# 101_Power.net
KiCad netlist of a schematic drawn in Altium Designer
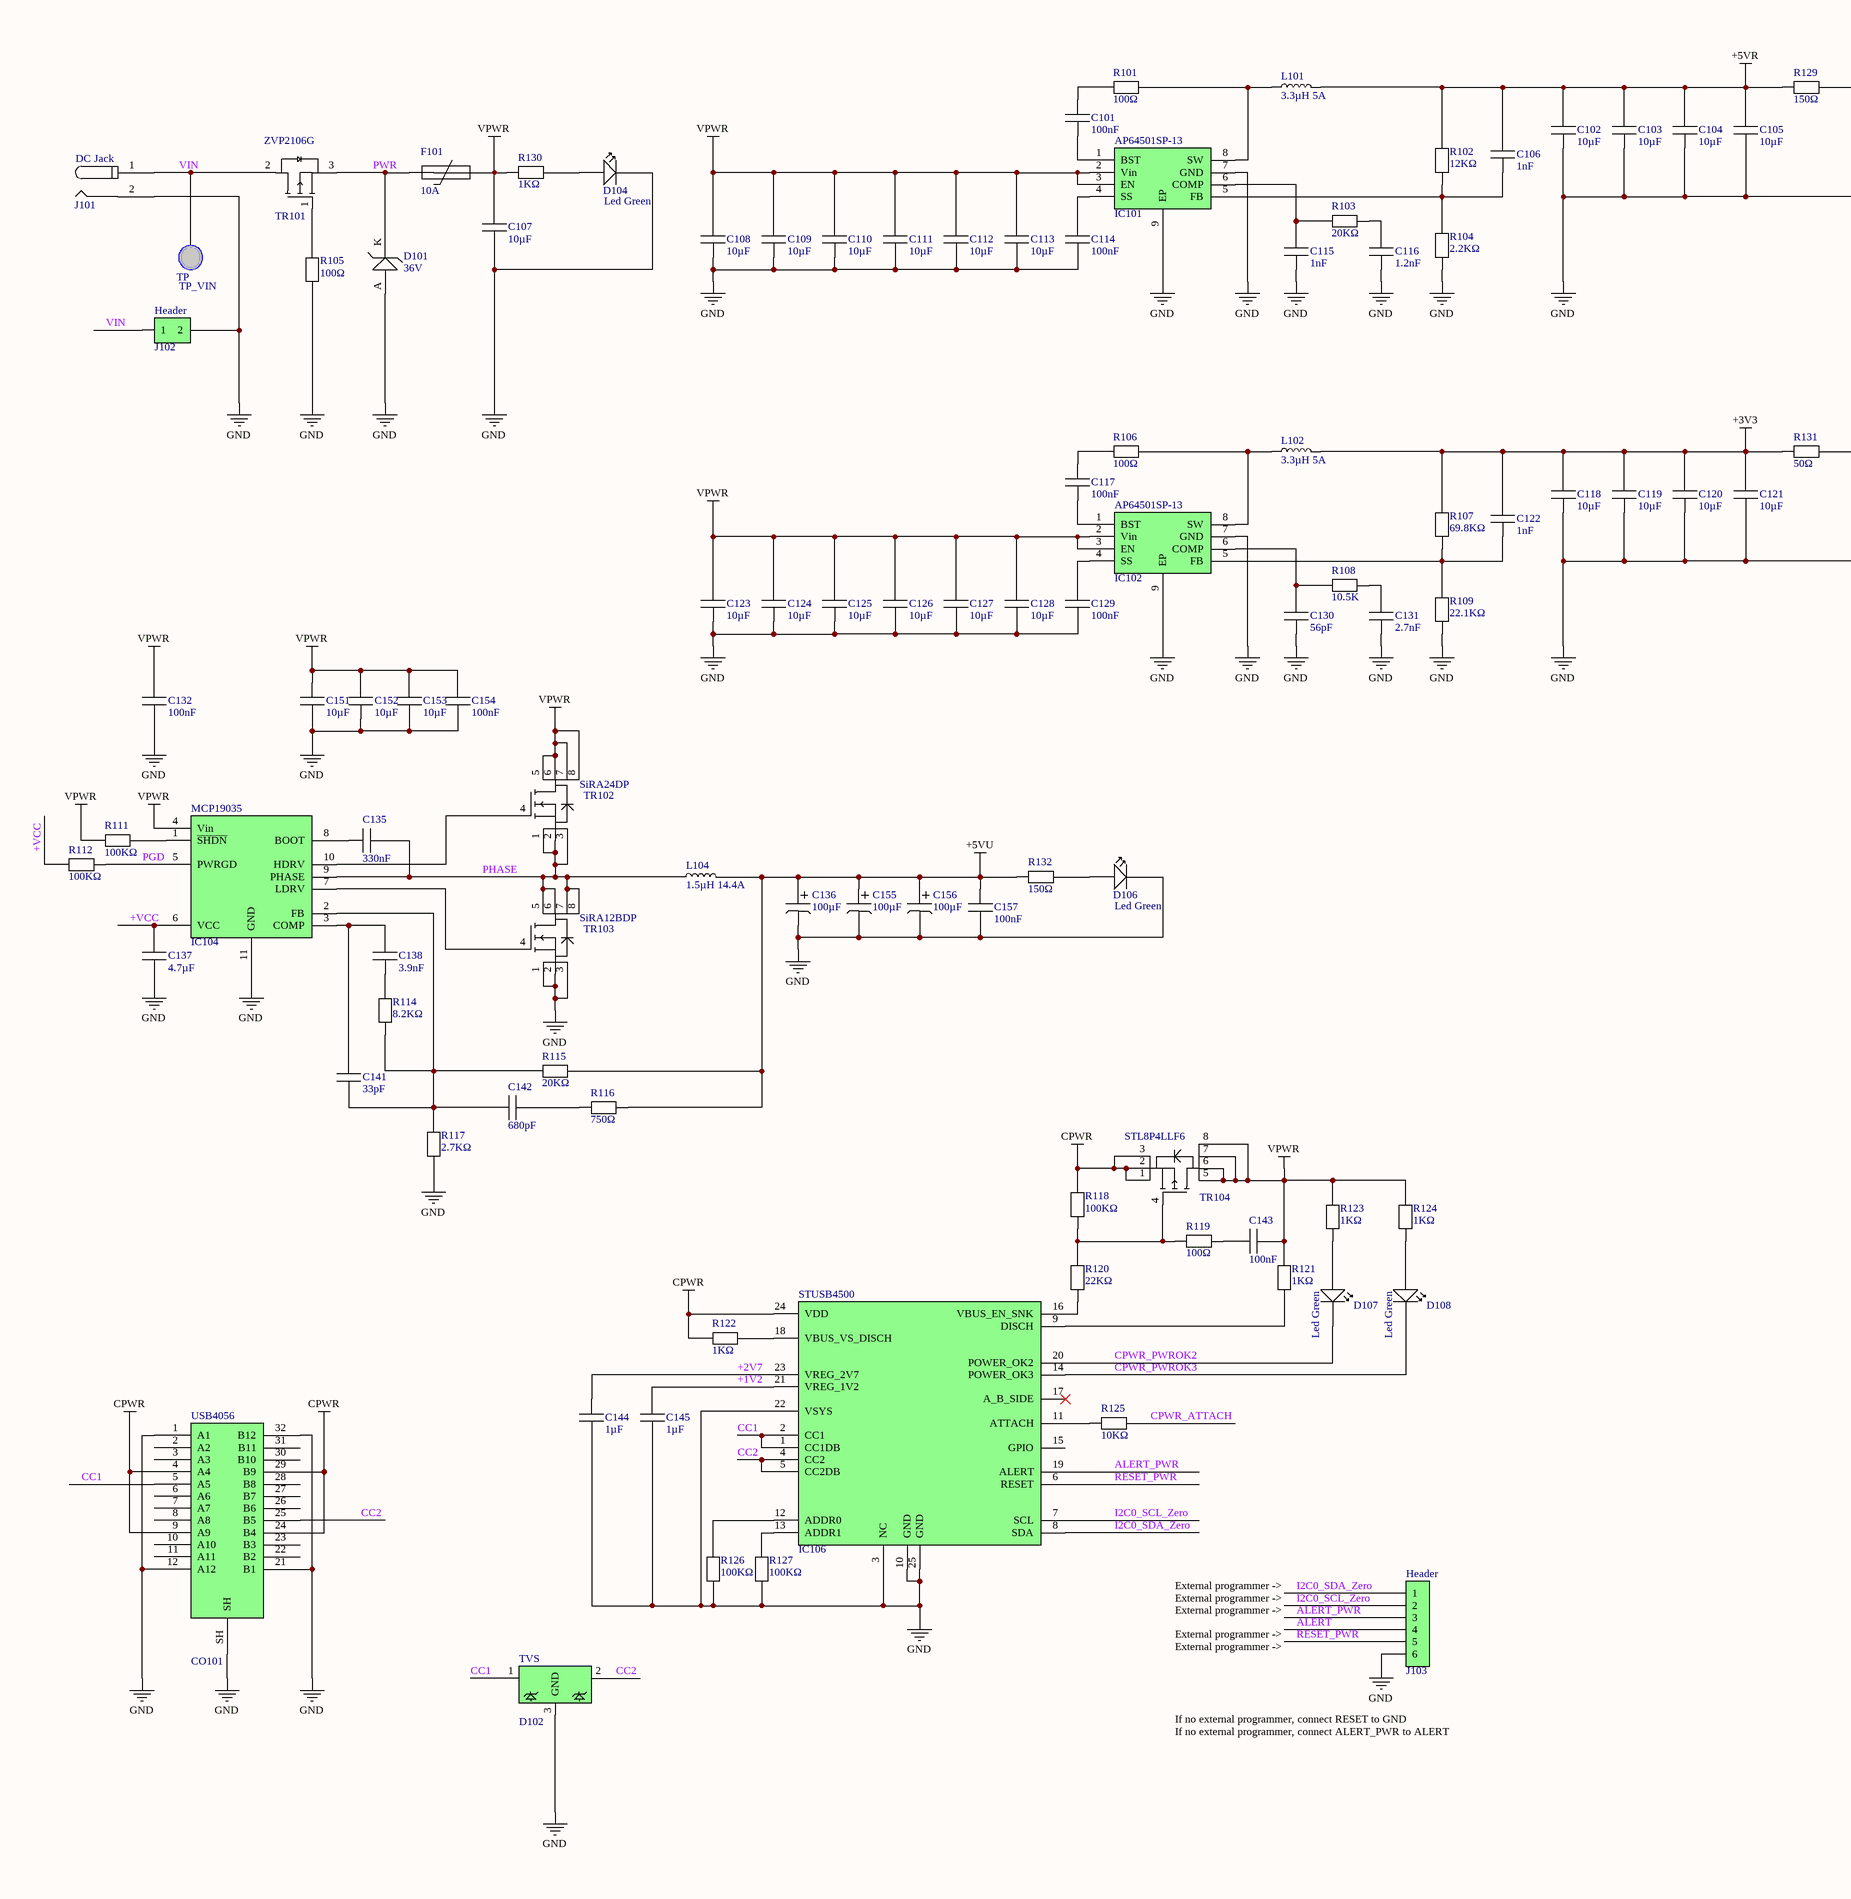
[diagram p0: 101_Power.SchDoc, left]
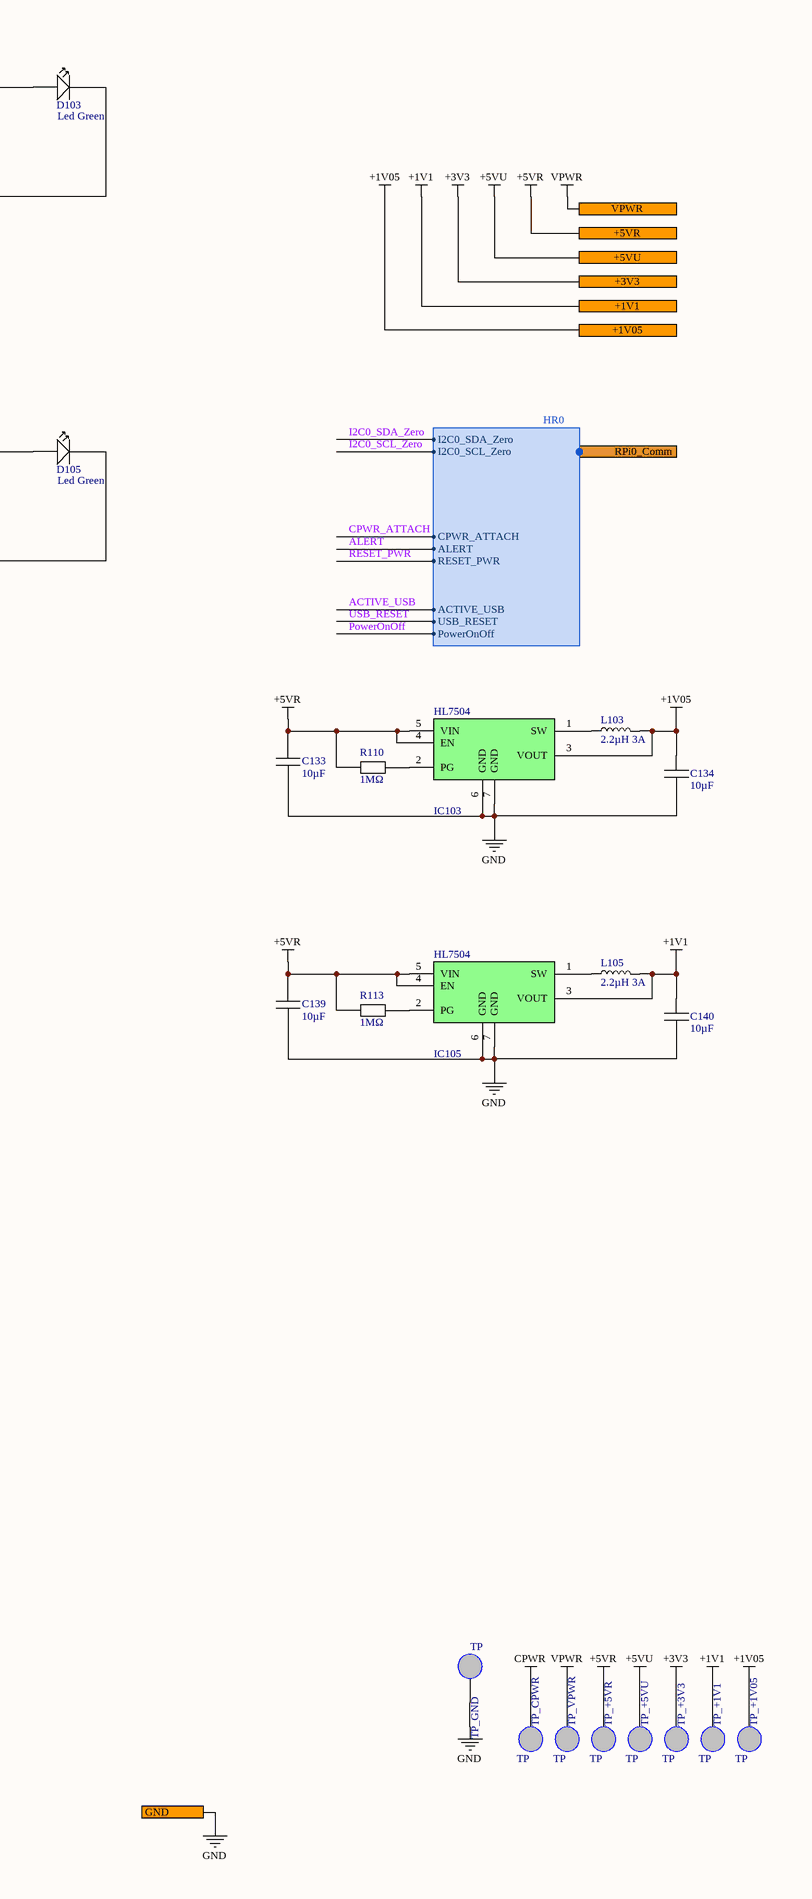
[diagram p1: 101_Power.SchDoc, right]

(export (version "E")
  (design (tool "Eeschema 10.0.6"))
  (components
    (comp (ref "C101")
      (value "100nF")
      (footprint "C0402")
      (description "100nF 50V 10% X7R")
      (fields
        (field (name "REFVAL") "100nF")
        (field (name "PART NUMBER") "CA0029")
        (field (name "MANFACTPART") "CGA2B3X7R1H104K050BB")
      )
      (libsource (lib "GTS_Database") (part "C"))
    )
    (comp (ref "C102")
      (value "10µF")
      (footprint "C0805")
      (description "10µF 16V 10% X5R")
      (fields
        (field (name "REFVAL") "10µF")
        (field (name "PART NUMBER") "CA0001")
        (field (name "MANFACTPART") "GRM21BR61C106KE15L")
      )
      (libsource (lib "GTS_Database") (part "C"))
    )
    (comp (ref "C103")
      (value "10µF")
      (footprint "C0805")
      (description "10µF 16V 10% X5R")
      (fields
        (field (name "REFVAL") "10µF")
        (field (name "PART NUMBER") "CA0001")
        (field (name "MANFACTPART") "GRM21BR61C106KE15L")
      )
      (libsource (lib "GTS_Database") (part "C"))
    )
    (comp (ref "C104")
      (value "10µF")
      (footprint "C0805")
      (description "10µF 16V 10% X5R")
      (fields
        (field (name "REFVAL") "10µF")
        (field (name "PART NUMBER") "CA0001")
        (field (name "MANFACTPART") "GRM21BR61C106KE15L")
      )
      (libsource (lib "GTS_Database") (part "C"))
    )
    (comp (ref "C105")
      (value "10µF")
      (footprint "C0805")
      (description "10µF 16V 10% X5R")
      (fields
        (field (name "REFVAL") "10µF")
        (field (name "PART NUMBER") "CA0001")
        (field (name "MANFACTPART") "GRM21BR61C106KE15L")
      )
      (libsource (lib "GTS_Database") (part "C"))
    )
    (comp (ref "C106")
      (value "1nF")
      (footprint "C0402")
      (description "1nF 50V 1% C0G")
      (fields
        (field (name "REFVAL") "1nF")
        (field (name "PART NUMBER") "CA0031")
        (field (name "MANFACTPART") "GRT1555C1H102FA02D")
      )
      (libsource (lib "GTS_Database") (part "C"))
    )
    (comp (ref "C107")
      (value "10µF")
      (footprint "C1210")
      (description "10µF 63V 10% X7R")
      (fields
        (field (name "REFVAL") "10µF")
        (field (name "PART NUMBER") "CA0024")
        (field (name "MANFACTPART") "GRM32ER71J106KA12")
      )
      (libsource (lib "GTS_Database") (part "C"))
    )
    (comp (ref "C108")
      (value "10µF")
      (footprint "C0805")
      (description "10µF 35V 10% X5R")
      (fields
        (field (name "REFVAL") "10µF")
        (field (name "PART NUMBER") "CA0005")
        (field (name "MANFACTPART") "C2012X5R1V106K125AC")
      )
      (libsource (lib "GTS_Database") (part "C"))
    )
    (comp (ref "C109")
      (value "10µF")
      (footprint "C0805")
      (description "10µF 35V 10% X5R")
      (fields
        (field (name "REFVAL") "10µF")
        (field (name "PART NUMBER") "CA0005")
        (field (name "MANFACTPART") "C2012X5R1V106K125AC")
      )
      (libsource (lib "GTS_Database") (part "C"))
    )
    (comp (ref "C110")
      (value "10µF")
      (footprint "C0805")
      (description "10µF 35V 10% X5R")
      (fields
        (field (name "REFVAL") "10µF")
        (field (name "PART NUMBER") "CA0005")
        (field (name "MANFACTPART") "C2012X5R1V106K125AC")
      )
      (libsource (lib "GTS_Database") (part "C"))
    )
    (comp (ref "C111")
      (value "10µF")
      (footprint "C0805")
      (description "10µF 35V 10% X5R")
      (fields
        (field (name "REFVAL") "10µF")
        (field (name "PART NUMBER") "CA0005")
        (field (name "MANFACTPART") "C2012X5R1V106K125AC")
      )
      (libsource (lib "GTS_Database") (part "C"))
    )
    (comp (ref "C112")
      (value "10µF")
      (footprint "C0805")
      (description "10µF 35V 10% X5R")
      (fields
        (field (name "REFVAL") "10µF")
        (field (name "PART NUMBER") "CA0005")
        (field (name "MANFACTPART") "C2012X5R1V106K125AC")
      )
      (libsource (lib "GTS_Database") (part "C"))
    )
    (comp (ref "C113")
      (value "10µF")
      (footprint "C0805")
      (description "10µF 35V 10% X5R")
      (fields
        (field (name "REFVAL") "10µF")
        (field (name "PART NUMBER") "CA0005")
        (field (name "MANFACTPART") "C2012X5R1V106K125AC")
      )
      (libsource (lib "GTS_Database") (part "C"))
    )
    (comp (ref "C114")
      (value "100nF")
      (footprint "C0402")
      (description "100nF 50V 10% X7R")
      (fields
        (field (name "REFVAL") "100nF")
        (field (name "PART NUMBER") "CA0029")
        (field (name "MANFACTPART") "CGA2B3X7R1H104K050BB")
      )
      (libsource (lib "GTS_Database") (part "C"))
    )
    (comp (ref "C115")
      (value "1nF")
      (footprint "C0402")
      (description "1nF 50V 1% C0G")
      (fields
        (field (name "REFVAL") "1nF")
        (field (name "PART NUMBER") "CA0031")
        (field (name "MANFACTPART") "GRT1555C1H102FA02D")
      )
      (libsource (lib "GTS_Database") (part "C"))
    )
    (comp (ref "C116")
      (value "1.2nF")
      (footprint "C0402")
      (description "1.2nF 50V 10% X7R")
      (fields
        (field (name "REFVAL") "1.2nF")
        (field (name "PART NUMBER") "CA0030")
        (field (name "MANFACTPART") "GCM155R71H122KA37D")
      )
      (libsource (lib "GTS_Database") (part "C"))
    )
    (comp (ref "C117")
      (value "100nF")
      (footprint "C0402")
      (description "100nF 50V 10% X7R")
      (fields
        (field (name "REFVAL") "100nF")
        (field (name "PART NUMBER") "CA0029")
        (field (name "MANFACTPART") "CGA2B3X7R1H104K050BB")
      )
      (libsource (lib "GTS_Database") (part "C"))
    )
    (comp (ref "C118")
      (value "10µF")
      (footprint "C0805")
      (description "10µF 16V 10% X5R")
      (fields
        (field (name "REFVAL") "10µF")
        (field (name "PART NUMBER") "CA0001")
        (field (name "MANFACTPART") "GRM21BR61C106KE15L")
      )
      (libsource (lib "GTS_Database") (part "C"))
    )
    (comp (ref "C119")
      (value "10µF")
      (footprint "C0805")
      (description "10µF 16V 10% X5R")
      (fields
        (field (name "REFVAL") "10µF")
        (field (name "PART NUMBER") "CA0001")
        (field (name "MANFACTPART") "GRM21BR61C106KE15L")
      )
      (libsource (lib "GTS_Database") (part "C"))
    )
    (comp (ref "C120")
      (value "10µF")
      (footprint "C0805")
      (description "10µF 16V 10% X5R")
      (fields
        (field (name "REFVAL") "10µF")
        (field (name "PART NUMBER") "CA0001")
        (field (name "MANFACTPART") "GRM21BR61C106KE15L")
      )
      (libsource (lib "GTS_Database") (part "C"))
    )
    (comp (ref "C121")
      (value "10µF")
      (footprint "C0805")
      (description "10µF 16V 10% X5R")
      (fields
        (field (name "REFVAL") "10µF")
        (field (name "PART NUMBER") "CA0001")
        (field (name "MANFACTPART") "GRM21BR61C106KE15L")
      )
      (libsource (lib "GTS_Database") (part "C"))
    )
    (comp (ref "C122")
      (value "1nF")
      (footprint "C0402")
      (description "1nF 50V 1% C0G")
      (fields
        (field (name "REFVAL") "1nF")
        (field (name "PART NUMBER") "CA0031")
        (field (name "MANFACTPART") "GRT1555C1H102FA02D")
      )
      (libsource (lib "GTS_Database") (part "C"))
    )
    (comp (ref "C123")
      (value "10µF")
      (footprint "C0805")
      (description "10µF 35V 10% X5R")
      (fields
        (field (name "REFVAL") "10µF")
        (field (name "PART NUMBER") "CA0005")
        (field (name "MANFACTPART") "C2012X5R1V106K125AC")
      )
      (libsource (lib "GTS_Database") (part "C"))
    )
    (comp (ref "C124")
      (value "10µF")
      (footprint "C0805")
      (description "10µF 35V 10% X5R")
      (fields
        (field (name "REFVAL") "10µF")
        (field (name "PART NUMBER") "CA0005")
        (field (name "MANFACTPART") "C2012X5R1V106K125AC")
      )
      (libsource (lib "GTS_Database") (part "C"))
    )
    (comp (ref "C125")
      (value "10µF")
      (footprint "C0805")
      (description "10µF 35V 10% X5R")
      (fields
        (field (name "REFVAL") "10µF")
        (field (name "PART NUMBER") "CA0005")
        (field (name "MANFACTPART") "C2012X5R1V106K125AC")
      )
      (libsource (lib "GTS_Database") (part "C"))
    )
    (comp (ref "C126")
      (value "10µF")
      (footprint "C0805")
      (description "10µF 35V 10% X5R")
      (fields
        (field (name "REFVAL") "10µF")
        (field (name "PART NUMBER") "CA0005")
        (field (name "MANFACTPART") "C2012X5R1V106K125AC")
      )
      (libsource (lib "GTS_Database") (part "C"))
    )
    (comp (ref "C127")
      (value "10µF")
      (footprint "C0805")
      (description "10µF 35V 10% X5R")
      (fields
        (field (name "REFVAL") "10µF")
        (field (name "PART NUMBER") "CA0005")
        (field (name "MANFACTPART") "C2012X5R1V106K125AC")
      )
      (libsource (lib "GTS_Database") (part "C"))
    )
    (comp (ref "C128")
      (value "10µF")
      (footprint "C0805")
      (description "10µF 35V 10% X5R")
      (fields
        (field (name "REFVAL") "10µF")
        (field (name "PART NUMBER") "CA0005")
        (field (name "MANFACTPART") "C2012X5R1V106K125AC")
      )
      (libsource (lib "GTS_Database") (part "C"))
    )
    (comp (ref "C129")
      (value "100nF")
      (footprint "C0402")
      (description "100nF 50V 10% X7R")
      (fields
        (field (name "REFVAL") "100nF")
        (field (name "PART NUMBER") "CA0029")
        (field (name "MANFACTPART") "CGA2B3X7R1H104K050BB")
      )
      (libsource (lib "GTS_Database") (part "C"))
    )
    (comp (ref "C130")
      (value "56pF")
      (footprint "C0402")
      (description "56pF 50V 2% C0G")
      (fields
        (field (name "REFVAL") "56pF")
        (field (name "PART NUMBER") "CA0068")
        (field (name "MANFACTPART") "CC0402GRNPO9BN560")
      )
      (libsource (lib "GTS_Database") (part "C"))
    )
    (comp (ref "C131")
      (value "2.7nF")
      (footprint "C0402")
      (description "2.7nF 50V 5% X7R")
      (fields
        (field (name "REFVAL") "2.7nF")
        (field (name "PART NUMBER") "CA0055")
        (field (name "MANFACTPART") "GRM155R71H272JA01D")
      )
      (libsource (lib "GTS_Database") (part "C"))
    )
    (comp (ref "C132")
      (value "100nF")
      (footprint "C0805")
      (description "100nF 50V 20% X7R")
      (fields
        (field (name "REFVAL") "100nF")
        (field (name "PART NUMBER") "CA0023")
        (field (name "MANFACTPART") "C0805C104M5RAC")
      )
      (libsource (lib "GTS_Database") (part "C"))
    )
    (comp (ref "C133")
      (value "10µF")
      (footprint "C0603")
      (description "10µF 16V 20% X5R")
      (fields
        (field (name "REFVAL") "10µF")
        (field (name "PART NUMBER") "CA0008")
        (field (name "MANFACTPART") "GRM188R61C106MAALD")
      )
      (libsource (lib "GTS_Database") (part "C"))
    )
    (comp (ref "C134")
      (value "10µF")
      (footprint "C0603")
      (description "10µF 16V 20% X5R")
      (fields
        (field (name "REFVAL") "10µF")
        (field (name "PART NUMBER") "CA0008")
        (field (name "MANFACTPART") "GRM188R61C106MAALD")
      )
      (libsource (lib "GTS_Database") (part "C"))
    )
    (comp (ref "C135")
      (value "330nF")
      (footprint "C0603")
      (description "330nF 35V 10% X5R")
      (fields
        (field (name "REFVAL") "330nF")
        (field (name "PART NUMBER") "CA0004")
        (field (name "MANFACTPART") "CGA3E3X5R1V334K080AB")
      )
      (libsource (lib "GTS_Database") (part "C"))
    )
    (comp (ref "C136")
      (value "100µF")
      (footprint "RL_6.3_2.5_11")
      (description "100µF 35V 20% 231mA")
      (fields
        (field (name "REFVAL") "100µF")
        (field (name "PART NUMBER") "CA0050")
        (field (name "MANFACTPART") "860010573007")
      )
      (libsource (lib "GTS_Database") (part "C+"))
    )
    (comp (ref "C137")
      (value "4.7µF")
      (footprint "C0603")
      (description "4.7µF 16V 10% X5R")
      (fields
        (field (name "REFVAL") "4.7µF")
        (field (name "PART NUMBER") "CA0002")
        (field (name "MANFACTPART") "C1608X5R1C475K080AC")
      )
      (libsource (lib "GTS_Database") (part "C"))
    )
    (comp (ref "C138")
      (value "3.9nF")
      (footprint "C0402")
      (description "3.9nF 50V 10% X7R")
      (fields
        (field (name "REFVAL") "3.9nF")
        (field (name "PART NUMBER") "CA0066")
        (field (name "MANFACTPART") "GCM155R71H392KA37D")
      )
      (libsource (lib "GTS_Database") (part "C"))
    )
    (comp (ref "C139")
      (value "10µF")
      (footprint "C0603")
      (description "10µF 16V 20% X5R")
      (fields
        (field (name "REFVAL") "10µF")
        (field (name "PART NUMBER") "CA0008")
        (field (name "MANFACTPART") "GRM188R61C106MAALD")
      )
      (libsource (lib "GTS_Database") (part "C"))
    )
    (comp (ref "C140")
      (value "10µF")
      (footprint "C0603")
      (description "10µF 16V 20% X5R")
      (fields
        (field (name "REFVAL") "10µF")
        (field (name "PART NUMBER") "CA0008")
        (field (name "MANFACTPART") "GRM188R61C106MAALD")
      )
      (libsource (lib "GTS_Database") (part "C"))
    )
    (comp (ref "C141")
      (value "33pF")
      (footprint "C0402")
      (description "33pF 50V 5% C0G")
      (fields
        (field (name "REFVAL") "33pF")
        (field (name "PART NUMBER") "CA0067")
        (field (name "MANFACTPART") "C1005C0G1H330J050BA")
      )
      (libsource (lib "GTS_Database") (part "C"))
    )
    (comp (ref "C142")
      (value "680pF")
      (footprint "C0402")
      (description "680pF 50V 10% X7R")
      (fields
        (field (name "REFVAL") "680pF")
        (field (name "PART NUMBER") "CA0065")
        (field (name "MANFACTPART") "C0402C681K5RAC")
      )
      (libsource (lib "GTS_Database") (part "C"))
    )
    (comp (ref "C143")
      (value "100nF")
      (footprint "C0402")
      (description "100nF 50V 10% X7R")
      (fields
        (field (name "REFVAL") "100nF")
        (field (name "PART NUMBER") "CA0029")
        (field (name "MANFACTPART") "CGA2B3X7R1H104K050BB")
      )
      (libsource (lib "GTS_Database") (part "C"))
    )
    (comp (ref "C144")
      (value "1µF")
      (footprint "C0603")
      (description "1µF 16V 10% X5R")
      (fields
        (field (name "REFVAL") "1µF")
        (field (name "PART NUMBER") "CA0003")
        (field (name "MANFACTPART") "C1608X5R1C105K080AA")
      )
      (libsource (lib "GTS_Database") (part "C"))
    )
    (comp (ref "C145")
      (value "1µF")
      (footprint "C0603")
      (description "1µF 16V 10% X5R")
      (fields
        (field (name "REFVAL") "1µF")
        (field (name "PART NUMBER") "CA0003")
        (field (name "MANFACTPART") "C1608X5R1C105K080AA")
      )
      (libsource (lib "GTS_Database") (part "C"))
    )
    (comp (ref "C151")
      (value "10µF")
      (footprint "C1210")
      (description "10µF 63V 10% X7R")
      (fields
        (field (name "REFVAL") "10µF")
        (field (name "PART NUMBER") "CA0024")
        (field (name "MANFACTPART") "GRM32ER71J106KA12")
      )
      (libsource (lib "GTS_Database") (part "C"))
    )
    (comp (ref "C152")
      (value "10µF")
      (footprint "C1210")
      (description "10µF 63V 10% X7R")
      (fields
        (field (name "REFVAL") "10µF")
        (field (name "PART NUMBER") "CA0024")
        (field (name "MANFACTPART") "GRM32ER71J106KA12")
      )
      (libsource (lib "GTS_Database") (part "C"))
    )
    (comp (ref "C153")
      (value "10µF")
      (footprint "C1210")
      (description "10µF 63V 10% X7R")
      (fields
        (field (name "REFVAL") "10µF")
        (field (name "PART NUMBER") "CA0024")
        (field (name "MANFACTPART") "GRM32ER71J106KA12")
      )
      (libsource (lib "GTS_Database") (part "C"))
    )
    (comp (ref "C154")
      (value "100nF")
      (footprint "C0805")
      (description "100nF 50V 20% X7R")
      (fields
        (field (name "REFVAL") "100nF")
        (field (name "PART NUMBER") "CA0023")
        (field (name "MANFACTPART") "C0805C104M5RAC")
      )
      (libsource (lib "GTS_Database") (part "C"))
    )
    (comp (ref "C155")
      (value "100µF")
      (footprint "RL_6.3_2.5_11")
      (description "100µF 35V 20% 231mA")
      (fields
        (field (name "REFVAL") "100µF")
        (field (name "PART NUMBER") "CA0050")
        (field (name "MANFACTPART") "860010573007")
      )
      (libsource (lib "GTS_Database") (part "C+"))
    )
    (comp (ref "C156")
      (value "100µF")
      (footprint "RL_6.3_2.5_11")
      (description "100µF 35V 20% 231mA")
      (fields
        (field (name "REFVAL") "100µF")
        (field (name "PART NUMBER") "CA0050")
        (field (name "MANFACTPART") "860010573007")
      )
      (libsource (lib "GTS_Database") (part "C+"))
    )
    (comp (ref "C157")
      (value "100nF")
      (footprint "C0805")
      (description "100nF 50V 20% X7R")
      (fields
        (field (name "REFVAL") "100nF")
        (field (name "PART NUMBER") "CA0023")
        (field (name "MANFACTPART") "C0805C104M5RAC")
      )
      (libsource (lib "GTS_Database") (part "C"))
    )
    (comp (ref "CO101")
      (value "USB4056")
      (footprint "USB4056-03-A")
      (description "USB C connector Receptacle Horizontal")
      (fields
        (field (name "REFVAL") "USB4056")
        (field (name "PART NUMBER") "CO0030")
        (field (name "MANFACTPART") "USB4056-03-A")
      )
      (libsource (lib "GTS_Database") (part "USB-CC"))
    )
    (comp (ref "D101")
      (value "36V")
      (footprint "SOD-323")
      (description "Zener Diode 36V 200mW")
      (fields
        (field (name "REFVAL") "36V")
        (field (name "PART NUMBER") "DI0008")
        (field (name "MANFACTPART") "BZT52C36S")
      )
      (libsource (lib "GTS_Database") (part "Dzener"))
    )
    (comp (ref "D102")
      (value "TVS")
      (footprint "SOT-323")
      (description "TRANSIL array for data protection")
      (fields
        (field (name "REFVAL") "TVS")
        (field (name "PART NUMBER") "DI0009")
        (field (name "MANFACTPART") "ESDA25W")
      )
      (libsource (lib "GTS_Database") (part "TVS_2P"))
    )
    (comp (ref "D103")
      (value "Led Green")
      (footprint "Led0805")
      (fields
        (field (name "REFVAL") "Led Green")
        (field (name "PART NUMBER") "DI0001")
        (field (name "MANFACTPART") "KP-2012CGCK")
      )
      (libsource (lib "GTS_Database") (part "Led"))
    )
    (comp (ref "D104")
      (value "Led Green")
      (footprint "Led0805")
      (fields
        (field (name "REFVAL") "Led Green")
        (field (name "PART NUMBER") "DI0001")
        (field (name "MANFACTPART") "KP-2012CGCK")
      )
      (libsource (lib "GTS_Database") (part "Led"))
    )
    (comp (ref "D105")
      (value "Led Green")
      (footprint "Led0805")
      (fields
        (field (name "REFVAL") "Led Green")
        (field (name "PART NUMBER") "DI0001")
        (field (name "MANFACTPART") "KP-2012CGCK")
      )
      (libsource (lib "GTS_Database") (part "Led"))
    )
    (comp (ref "D106")
      (value "Led Green")
      (footprint "Led0805")
      (fields
        (field (name "REFVAL") "Led Green")
        (field (name "PART NUMBER") "DI0001")
        (field (name "MANFACTPART") "KP-2012CGCK")
      )
      (libsource (lib "GTS_Database") (part "Led"))
    )
    (comp (ref "D107")
      (value "Led Green")
      (footprint "Led0805")
      (fields
        (field (name "REFVAL") "Led Green")
        (field (name "PART NUMBER") "DI0001")
        (field (name "MANFACTPART") "KP-2012CGCK")
      )
      (libsource (lib "GTS_Database") (part "Led"))
    )
    (comp (ref "D108")
      (value "Led Green")
      (footprint "Led0805")
      (fields
        (field (name "REFVAL") "Led Green")
        (field (name "PART NUMBER") "DI0001")
        (field (name "MANFACTPART") "KP-2012CGCK")
      )
      (libsource (lib "GTS_Database") (part "Led"))
    )
    (comp (ref "F101")
      (value "10A")
      (footprint "F1206")
      (description "32V/10A")
      (fields
        (field (name "REFVAL") "10A")
        (field (name "PART NUMBER") "F0004")
        (field (name "MANFACTPART") "C1H10")
      )
      (libsource (lib "GTS_Database") (part "F"))
    )
    (comp (ref "IC101")
      (value "AP64501SP-13")
      (footprint "SO-8-EP")
      (description "3.8V TO 40V INPUT, 5A LOW IQ SYNCHRONOUS BUCK WITH PROGRAMMABLE SOFT-START TIME")
      (fields (field (name "REFVAL") "AP64501SP-13") (field (name "PART NUMBER") "IC0031"))
      (libsource (lib "GTS_Database") (part "AP645"))
    )
    (comp (ref "IC102")
      (value "AP64501SP-13")
      (footprint "SO-8-EP")
      (description "3.8V TO 40V INPUT, 5A LOW IQ SYNCHRONOUS BUCK WITH PROGRAMMABLE SOFT-START TIME")
      (fields (field (name "REFVAL") "AP64501SP-13") (field (name "PART NUMBER") "IC0031"))
      (libsource (lib "GTS_Database") (part "AP645"))
    )
    (comp (ref "IC103")
      (value "HL7504")
      (footprint "DFN-6G_2X2")
      (description "3MHz 2A Buck Converter 1.05V OUT")
      (fields
        (field (name "REFVAL") "HL7504")
        (field (name "PART NUMBER") "IC0049")
        (field (name "MANFACTPART") "HL7504FN04")
      )
      (libsource (lib "GTS_Database") (part "HL7504"))
    )
    (comp (ref "IC104")
      (value "MCP19035")
      (footprint "DFN-10G_3X3")
      (description "Switching Controllers Synchronous Buck PWM Control 600kHz 12ns")
      (fields
        (field (name "REFVAL") "MCP19035")
        (field (name "PART NUMBER") "IC0055")
        (field (name "MANFACTPART") "MCP19035-BAABE/MF")
      )
      (libsource (lib "GTS_Database") (part "MCP19035"))
    )
    (comp (ref "IC105")
      (value "HL7504")
      (footprint "DFN-6G_2X2")
      (description "3MHz 2A Buck Converter 1.10V OUT")
      (fields
        (field (name "REFVAL") "HL7504")
        (field (name "PART NUMBER") "IC0050")
        (field (name "MANFACTPART") "HL7504FN08")
      )
      (libsource (lib "GTS_Database") (part "HL7504"))
    )
    (comp (ref "IC106")
      (value "STUSB4500")
      (footprint "QFN-24G_4X4")
      (description "USB Interface IC Standalone USB PD controller for power sinking devices")
      (fields
        (field (name "REFVAL") "STUSB4500")
        (field (name "PART NUMBER") "IC0057")
        (field (name "MANFACTPART") "STUSB4500QTR")
      )
      (libsource (lib "GTS_Database") (part "STUSB4500-QFN"))
    )
    (comp (ref "J101")
      (value "DC Jack")
      (footprint "PJ-082BH")
      (description "DC Jack 36V @10A")
      (fields
        (field (name "REFVAL") "DC Jack")
        (field (name "PART NUMBER") "CO0015")
        (field (name "MANFACTPART") "PJ-082BH")
      )
      (libsource (lib "GTS_Database") (part "DC_PWR_JACK_2P"))
    )
    (comp (ref "J102")
      (value "Header")
      (footprint "1X2P_2.54mm")
      (description "Header 1x2P")
      (fields
        (field (name "REFVAL") "Header")
        (field (name "PART NUMBER") "CO0012")
        (field (name "MANFACTPART") "G800W306018EU")
      )
      (libsource (lib "GTS_Database") (part "CONN1X2P"))
    )
    (comp (ref "J103")
      (value "Header")
      (footprint "1X6P_2.54MM_SMT")
      (description "Header 1x6P SMT Mount")
      (fields
        (field (name "REFVAL") "Header")
        (field (name "PART NUMBER") "CO0043")
        (field (name "MANFACTPART") "G800MJ302018EU")
      )
      (libsource (lib "GTS_Database") (part "CONN1X6P"))
    )
    (comp (ref "L101")
      (value "3.3µH 5A")
      (footprint "SRN6045TA")
      (description "3.3µH 5A 30% 21mΩ")
      (fields
        (field (name "REFVAL") "3.3µH 5A")
        (field (name "PART NUMBER") "IN0005")
        (field (name "MANFACTPART") "SRN6045TA-3R3Y")
      )
      (libsource (lib "GTS_Database") (part "L"))
    )
    (comp (ref "L102")
      (value "3.3µH 5A")
      (footprint "SRN6045TA")
      (description "3.3µH 5A 30% 21mΩ")
      (fields
        (field (name "REFVAL") "3.3µH 5A")
        (field (name "PART NUMBER") "IN0005")
        (field (name "MANFACTPART") "SRN6045TA-3R3Y")
      )
      (libsource (lib "GTS_Database") (part "L"))
    )
    (comp (ref "L103")
      (value "2.2µH 3A")
      (footprint "NRS4018")
      (fields
        (field (name "REFVAL") "2.2µH 3A")
        (field (name "PART NUMBER") "IN0004")
        (field (name "MANFACTPART") "NRS4018T2R2MDGJ")
      )
      (libsource (lib "GTS_Database") (part "L"))
    )
    (comp (ref "L104")
      (value "1.5µH 14.4A")
      (footprint "0630CDMCDDS")
      (description "1.5µH 14.4A 20% 7.4mΩ")
      (fields
        (field (name "REFVAL") "1.5µH 14.4A")
        (field (name "PART NUMBER") "IN0017")
        (field (name "MANFACTPART") "0630CDMCDDS-1R0MC")
      )
      (libsource (lib "GTS_Database") (part "L"))
    )
    (comp (ref "L105")
      (value "2.2µH 3A")
      (footprint "NRS4018")
      (fields
        (field (name "REFVAL") "2.2µH 3A")
        (field (name "PART NUMBER") "IN0004")
        (field (name "MANFACTPART") "NRS4018T2R2MDGJ")
      )
      (libsource (lib "GTS_Database") (part "L"))
    )
    (comp (ref "R101")
      (value "100Ω")
      (footprint "R0603")
      (description "100Ω 1% 100mW")
      (fields
        (field (name "REFVAL") "100Ω")
        (field (name "PART NUMBER") "RS0007")
        (field (name "MANFACTPART") "WR06X1000FTL")
      )
      (libsource (lib "GTS_Database") (part "R"))
    )
    (comp (ref "R102")
      (value "12KΩ")
      (footprint "R0402")
      (description "12KΩ 1% 62.5mW")
      (fields
        (field (name "REFVAL") "12KΩ")
        (field (name "PART NUMBER") "RS0015")
        (field (name "MANFACTPART") "RC0402FR-1312KL")
      )
      (libsource (lib "GTS_Database") (part "R"))
    )
    (comp (ref "R103")
      (value "20KΩ")
      (footprint "R0402")
      (description "20KΩ 1% 100mW 100PPM")
      (fields
        (field (name "REFVAL") "20KΩ")
        (field (name "PART NUMBER") "RS0034")
        (field (name "MANFACTPART") "ERJ-S02F2002X")
      )
      (libsource (lib "GTS_Database") (part "R"))
    )
    (comp (ref "R104")
      (value "2.2KΩ")
      (footprint "R0402")
      (description "2.2KΩ 1% 62.5mW 100PPM")
      (fields
        (field (name "REFVAL") "2.2KΩ")
        (field (name "PART NUMBER") "RS0035")
        (field (name "MANFACTPART") "CRGCQ0402F2K2")
      )
      (libsource (lib "GTS_Database") (part "R"))
    )
    (comp (ref "R105")
      (value "100Ω")
      (footprint "R0603")
      (description "100Ω 1% 100mW")
      (fields
        (field (name "REFVAL") "100Ω")
        (field (name "PART NUMBER") "RS0007")
        (field (name "MANFACTPART") "WR06X1000FTL")
      )
      (libsource (lib "GTS_Database") (part "R"))
    )
    (comp (ref "R106")
      (value "100Ω")
      (footprint "R0603")
      (description "100Ω 1% 100mW")
      (fields
        (field (name "REFVAL") "100Ω")
        (field (name "PART NUMBER") "RS0007")
        (field (name "MANFACTPART") "WR06X1000FTL")
      )
      (libsource (lib "GTS_Database") (part "R"))
    )
    (comp (ref "R107")
      (value "69.8KΩ")
      (footprint "R0603")
      (description "69.8KΩ 1% 100mW 100PPM")
      (fields
        (field (name "REFVAL") "69.8KΩ")
        (field (name "PART NUMBER") "RS0041")
        (field (name "MANFACTPART") "CRCW060369K8FKEB")
      )
      (libsource (lib "GTS_Database") (part "R"))
    )
    (comp (ref "R108")
      (value "10.5K")
      (footprint "R0402")
      (description "10.5KΩ 1% 62.5mW 100PPM")
      (fields
        (field (name "REFVAL") "10.5K")
        (field (name "PART NUMBER") "RS0054")
        (field (name "MANFACTPART") "CRCW040210K5FKEDC")
      )
      (libsource (lib "GTS_Database") (part "R"))
    )
    (comp (ref "R109")
      (value "22.1KΩ")
      (footprint "R0603")
      (description "22.1KΩ 1% 100mW 100PPM")
      (fields
        (field (name "REFVAL") "22.1KΩ")
        (field (name "PART NUMBER") "RS0040")
        (field (name "MANFACTPART") "RC0603FR-0722K1L")
      )
      (libsource (lib "GTS_Database") (part "R"))
    )
    (comp (ref "R110")
      (value "1MΩ")
      (footprint "R0402")
      (description "1MΩ 1% 62.5mW 100PPM")
      (fields
        (field (name "REFVAL") "1MΩ")
        (field (name "PART NUMBER") "RS0066")
        (field (name "MANFACTPART") "0402WGF1004TCE")
      )
      (libsource (lib "GTS_Database") (part "R"))
    )
    (comp (ref "R111")
      (value "100KΩ")
      (footprint "R0402")
      (description "100KΩ 1% 62.5mW 100PPM")
      (fields
        (field (name "REFVAL") "100KΩ")
        (field (name "PART NUMBER") "RS0036")
        (field (name "MANFACTPART") "AC0402FR-13100KL")
      )
      (libsource (lib "GTS_Database") (part "R"))
    )
    (comp (ref "R112")
      (value "100KΩ")
      (footprint "R0402")
      (description "100KΩ 1% 62.5mW 100PPM")
      (fields
        (field (name "REFVAL") "100KΩ")
        (field (name "PART NUMBER") "RS0036")
        (field (name "MANFACTPART") "AC0402FR-13100KL")
      )
      (libsource (lib "GTS_Database") (part "R"))
    )
    (comp (ref "R113")
      (value "1MΩ")
      (footprint "R0402")
      (description "1MΩ 1% 62.5mW 100PPM")
      (fields
        (field (name "REFVAL") "1MΩ")
        (field (name "PART NUMBER") "RS0066")
        (field (name "MANFACTPART") "0402WGF1004TCE")
      )
      (libsource (lib "GTS_Database") (part "R"))
    )
    (comp (ref "R114")
      (value "8.2KΩ")
      (footprint "R0402")
      (description "8.2KΩ 1% 62.5mW 100PPM")
      (fields
        (field (name "REFVAL") "8.2KΩ")
        (field (name "PART NUMBER") "RS0079")
        (field (name "MANFACTPART") "0402WGF8201TCE")
      )
      (libsource (lib "GTS_Database") (part "R"))
    )
    (comp (ref "R115")
      (value "20KΩ")
      (footprint "R0402")
      (description "20KΩ 1% 100mW 100PPM")
      (fields
        (field (name "REFVAL") "20KΩ")
        (field (name "PART NUMBER") "RS0034")
        (field (name "MANFACTPART") "ERJ-S02F2002X")
      )
      (libsource (lib "GTS_Database") (part "R"))
    )
    (comp (ref "R116")
      (value "750Ω")
      (footprint "R0402")
      (description "750Ω 1% 62.5mW 100PPM")
      (fields
        (field (name "REFVAL") "750Ω")
        (field (name "PART NUMBER") "RS0078")
        (field (name "MANFACTPART") "CRG0402F750R")
      )
      (libsource (lib "GTS_Database") (part "R"))
    )
    (comp (ref "R117")
      (value "2.7KΩ")
      (footprint "R0402")
      (description "2.7KΩ 1% 62.5mW 100PPM")
      (fields
        (field (name "REFVAL") "2.7KΩ")
        (field (name "PART NUMBER") "RS0059")
        (field (name "MANFACTPART") "CRG0402F2K7")
      )
      (libsource (lib "GTS_Database") (part "R"))
    )
    (comp (ref "R118")
      (value "100KΩ")
      (footprint "R0402")
      (description "100KΩ 1% 62.5mW 100PPM")
      (fields
        (field (name "REFVAL") "100KΩ")
        (field (name "PART NUMBER") "RS0036")
        (field (name "MANFACTPART") "AC0402FR-13100KL")
      )
      (libsource (lib "GTS_Database") (part "R"))
    )
    (comp (ref "R119")
      (value "100Ω")
      (footprint "R0603")
      (description "100Ω 1% 100mW")
      (fields
        (field (name "REFVAL") "100Ω")
        (field (name "PART NUMBER") "RS0007")
        (field (name "MANFACTPART") "WR06X1000FTL")
      )
      (libsource (lib "GTS_Database") (part "R"))
    )
    (comp (ref "R120")
      (value "22KΩ")
      (footprint "R0402")
      (description "22KΩ 1% 62.5mW 100PPM")
      (fields
        (field (name "REFVAL") "22KΩ")
        (field (name "PART NUMBER") "RS0033")
        (field (name "MANFACTPART") "MCWR04X2202FTL")
      )
      (libsource (lib "GTS_Database") (part "R"))
    )
    (comp (ref "R121")
      (value "1KΩ")
      (footprint "R0603")
      (description "1KΩ 5% 100mW")
      (fields
        (field (name "REFVAL") "1KΩ")
        (field (name "PART NUMBER") "RS0008")
        (field (name "MANFACTPART") "WR06X102 JTL")
      )
      (libsource (lib "GTS_Database") (part "R"))
    )
    (comp (ref "R122")
      (value "1KΩ")
      (footprint "R0603")
      (description "1KΩ 5% 100mW")
      (fields
        (field (name "REFVAL") "1KΩ")
        (field (name "PART NUMBER") "RS0008")
        (field (name "MANFACTPART") "WR06X102 JTL")
      )
      (libsource (lib "GTS_Database") (part "R"))
    )
    (comp (ref "R123")
      (value "1KΩ")
      (footprint "R0402")
      (description "1KΩ 5% 62.5mW 100PPM")
      (fields
        (field (name "REFVAL") "1KΩ")
        (field (name "PART NUMBER") "RS0037")
        (field (name "MANFACTPART") "RC0402JR-131KL")
      )
      (libsource (lib "GTS_Database") (part "R"))
    )
    (comp (ref "R124")
      (value "1KΩ")
      (footprint "R0402")
      (description "1KΩ 5% 62.5mW 100PPM")
      (fields
        (field (name "REFVAL") "1KΩ")
        (field (name "PART NUMBER") "RS0037")
        (field (name "MANFACTPART") "RC0402JR-131KL")
      )
      (libsource (lib "GTS_Database") (part "R"))
    )
    (comp (ref "R125")
      (value "10KΩ")
      (footprint "R0402")
      (description "10KΩ 1% 62.5mW")
      (fields
        (field (name "REFVAL") "10KΩ")
        (field (name "PART NUMBER") "RS0011")
        (field (name "MANFACTPART") "WR04X1002FTL")
      )
      (libsource (lib "GTS_Database") (part "R"))
    )
    (comp (ref "R126")
      (value "100KΩ")
      (footprint "R0402")
      (description "100KΩ 1% 62.5mW 100PPM")
      (fields
        (field (name "REFVAL") "100KΩ")
        (field (name "PART NUMBER") "RS0036")
        (field (name "MANFACTPART") "AC0402FR-13100KL")
      )
      (libsource (lib "GTS_Database") (part "R"))
    )
    (comp (ref "R127")
      (value "100KΩ")
      (footprint "R0402")
      (description "100KΩ 1% 62.5mW 100PPM")
      (fields
        (field (name "REFVAL") "100KΩ")
        (field (name "PART NUMBER") "RS0036")
        (field (name "MANFACTPART") "AC0402FR-13100KL")
      )
      (libsource (lib "GTS_Database") (part "R"))
    )
    (comp (ref "R129")
      (value "150Ω")
      (footprint "R0603")
      (description "150Ω 1% 100mW")
      (fields
        (field (name "REFVAL") "150Ω")
        (field (name "PART NUMBER") "RS0001")
        (field (name "MANFACTPART") "MCWR06X1500FTL")
      )
      (libsource (lib "GTS_Database") (part "R"))
    )
    (comp (ref "R130")
      (value "1KΩ")
      (footprint "R0603")
      (description "1KΩ 5% 100mW")
      (fields
        (field (name "REFVAL") "1KΩ")
        (field (name "PART NUMBER") "RS0008")
        (field (name "MANFACTPART") "WR06X102 JTL")
      )
      (libsource (lib "GTS_Database") (part "R"))
    )
    (comp (ref "R131")
      (value "50Ω")
      (footprint "R0603")
      (description "50Ω 0.1% 100mW 50PPM")
      (fields
        (field (name "REFVAL") "50Ω")
        (field (name "PART NUMBER") "RS0080")
        (field (name "MANFACTPART") "RT0603BRE0750RL")
      )
      (libsource (lib "GTS_Database") (part "R"))
    )
    (comp (ref "R132")
      (value "150Ω")
      (footprint "R0603")
      (description "150Ω 1% 100mW")
      (fields
        (field (name "REFVAL") "150Ω")
        (field (name "PART NUMBER") "RS0001")
        (field (name "MANFACTPART") "MCWR06X1500FTL")
      )
      (libsource (lib "GTS_Database") (part "R"))
    )
    (comp (ref "TP_+1V1")
      (value "TP")
      (footprint "TP_1MM")
      (description "Testpoint 1mm")
      (fields (field (name "REFVAL") "TP") (field (name "PART NUMBER") "ME0027"))
      (libsource (lib "GTS_Database") (part "TP"))
    )
    (comp (ref "TP_+1V05")
      (value "TP")
      (footprint "TP_1MM")
      (description "Testpoint 1mm")
      (fields (field (name "REFVAL") "TP") (field (name "PART NUMBER") "ME0027"))
      (libsource (lib "GTS_Database") (part "TP"))
    )
    (comp (ref "TP_+3V3")
      (value "TP")
      (footprint "TP_1MM")
      (description "Testpoint 1mm")
      (fields (field (name "REFVAL") "TP") (field (name "PART NUMBER") "ME0027"))
      (libsource (lib "GTS_Database") (part "TP"))
    )
    (comp (ref "TP_+5VR")
      (value "TP")
      (footprint "TP_1MM")
      (description "Testpoint 1mm")
      (fields (field (name "REFVAL") "TP") (field (name "PART NUMBER") "ME0027"))
      (libsource (lib "GTS_Database") (part "TP"))
    )
    (comp (ref "TP_+5VU")
      (value "TP")
      (footprint "TP_1MM")
      (description "Testpoint 1mm")
      (fields (field (name "REFVAL") "TP") (field (name "PART NUMBER") "ME0027"))
      (libsource (lib "GTS_Database") (part "TP"))
    )
    (comp (ref "TP_CPWR")
      (value "TP")
      (footprint "TP_1MM")
      (description "Testpoint 1mm")
      (fields (field (name "REFVAL") "TP") (field (name "PART NUMBER") "ME0027"))
      (libsource (lib "GTS_Database") (part "TP"))
    )
    (comp (ref "TP_GND")
      (value "TP")
      (footprint "TP_1MM")
      (description "Testpoint 1mm")
      (fields (field (name "REFVAL") "TP") (field (name "PART NUMBER") "ME0027"))
      (libsource (lib "GTS_Database") (part "TP"))
    )
    (comp (ref "TP_VIN")
      (value "TP")
      (footprint "TP_1MM")
      (description "Testpoint 1mm")
      (fields (field (name "REFVAL") "TP") (field (name "PART NUMBER") "ME0027"))
      (libsource (lib "GTS_Database") (part "TP"))
    )
    (comp (ref "TP_VPWR")
      (value "TP")
      (footprint "TP_1MM")
      (description "Testpoint 1mm")
      (fields (field (name "REFVAL") "TP") (field (name "PART NUMBER") "ME0027"))
      (libsource (lib "GTS_Database") (part "TP"))
    )
    (comp (ref "TR101")
      (value "ZVP2106G")
      (footprint "SOT-223")
      (description "36V-PNP-E")
      (fields
        (field (name "REFVAL") "ZVP2106G")
        (field (name "PART NUMBER") "TR0007")
        (field (name "MANFACTPART") "ZVP2106GTA")
      )
      (libsource (lib "GTS_Database") (part "MOS_E_P_1G2D3S"))
    )
    (comp (ref "TR102")
      (value "SiRA24DP")
      (footprint "PowerPAK-SO-8_5X6")
      (description "25V/2.4mΩ, N-channel Power MOSFET, 35.6A")
      (fields
        (field (name "REFVAL") "SiRA24DP")
        (field (name "PART NUMBER") "TR0012")
        (field (name "MANFACTPART") "SIRA24DP-T1-GE3")
      )
      (libsource (lib "GTS_Database") (part "MOS_E_N_4G5678D123S"))
    )
    (comp (ref "TR103")
      (value "SiRA12BDP")
      (footprint "PowerPAK-SO-8_5X6")
      (description "30V/6mΩ, N-channel Power MOSFET, 22A")
      (fields
        (field (name "REFVAL") "SiRA12BDP")
        (field (name "PART NUMBER") "TR0013")
        (field (name "MANFACTPART") "SIRA12BDP-T1-GE3")
      )
      (libsource (lib "GTS_Database") (part "MOS_E_N_4G5678D123S"))
    )
    (comp (ref "TR104")
      (value "STL8P4LLF6")
      (footprint "PowerFLAT-3.3x3.3-8")
      (description "40V/17.5mΩ, P-channel Trench MOSFET, 8A")
      (fields (field (name "REFVAL") "STL8P4LLF6") (field (name "PART NUMBER") "TR0010"))
      (libsource (lib "GTS_Database") (part "MOS_T_P_4G5678D123S"))
    )
  )
  (nets
    (net (code "2") (name "+1V1") (class "Default")
      (node (ref "C140") (pin "1") (pinfunction "1_1") (pintype "passive"))
      (node (ref "IC105") (pin "3") (pinfunction "VOUT_3") (pintype "passive"))
      (node (ref "L105") (pin "2") (pinfunction "2_2") (pintype "passive"))
      (node (ref "TP_+1V1") (pin "1") (pinfunction "1_1") (pintype "passive"))
    )
    (net (code "3") (name "+1V05") (class "Default")
      (node (ref "C134") (pin "1") (pinfunction "1_1") (pintype "passive"))
      (node (ref "IC103") (pin "3") (pinfunction "VOUT_3") (pintype "passive"))
      (node (ref "L103") (pin "2") (pinfunction "2_2") (pintype "passive"))
      (node (ref "TP_+1V05") (pin "1") (pinfunction "1_1") (pintype "passive"))
    )
    (net (code "4") (name "+3V3") (class "Default")
      (node (ref "C118") (pin "1") (pinfunction "1_1") (pintype "passive"))
      (node (ref "C119") (pin "1") (pinfunction "1_1") (pintype "passive"))
      (node (ref "C120") (pin "1") (pinfunction "1_1") (pintype "passive"))
      (node (ref "C121") (pin "1") (pinfunction "1_1") (pintype "passive"))
      (node (ref "C122") (pin "1") (pinfunction "1_1") (pintype "passive"))
      (node (ref "L102") (pin "2") (pinfunction "2_2") (pintype "passive"))
      (node (ref "R107") (pin "2") (pinfunction "2_2") (pintype "passive"))
      (node (ref "R131") (pin "1") (pinfunction "1_1") (pintype "passive"))
      (node (ref "TP_+3V3") (pin "1") (pinfunction "1_1") (pintype "passive"))
    )
    (net (code "5") (name "+5VR") (class "Default")
      (node (ref "C102") (pin "1") (pinfunction "1_1") (pintype "passive"))
      (node (ref "C103") (pin "1") (pinfunction "1_1") (pintype "passive"))
      (node (ref "C104") (pin "1") (pinfunction "1_1") (pintype "passive"))
      (node (ref "C105") (pin "1") (pinfunction "1_1") (pintype "passive"))
      (node (ref "C106") (pin "1") (pinfunction "1_1") (pintype "passive"))
      (node (ref "C133") (pin "1") (pinfunction "1_1") (pintype "passive"))
      (node (ref "C139") (pin "1") (pinfunction "1_1") (pintype "passive"))
      (node (ref "IC103") (pin "4") (pinfunction "EN_4") (pintype "passive"))
      (node (ref "IC103") (pin "5") (pinfunction "VIN_5") (pintype "passive"))
      (node (ref "IC105") (pin "4") (pinfunction "EN_4") (pintype "passive"))
      (node (ref "IC105") (pin "5") (pinfunction "VIN_5") (pintype "passive"))
      (node (ref "L101") (pin "2") (pinfunction "2_2") (pintype "passive"))
      (node (ref "R102") (pin "2") (pinfunction "2_2") (pintype "passive"))
      (node (ref "R110") (pin "1") (pinfunction "1_1") (pintype "passive"))
      (node (ref "R113") (pin "1") (pinfunction "1_1") (pintype "passive"))
      (node (ref "R129") (pin "1") (pinfunction "1_1") (pintype "passive"))
      (node (ref "TP_+5VR") (pin "1") (pinfunction "1_1") (pintype "passive"))
    )
    (net (code "6") (name "+5VU") (class "Default")
      (node (ref "C136") (pin "1") (pinfunction "1_1") (pintype "passive"))
      (node (ref "C155") (pin "1") (pinfunction "1_1") (pintype "passive"))
      (node (ref "C156") (pin "1") (pinfunction "1_1") (pintype "passive"))
      (node (ref "C157") (pin "1") (pinfunction "1_1") (pintype "passive"))
      (node (ref "L104") (pin "2") (pinfunction "2_2") (pintype "passive"))
      (node (ref "R115") (pin "2") (pinfunction "2_2") (pintype "passive"))
      (node (ref "R116") (pin "2") (pinfunction "2_2") (pintype "passive"))
      (node (ref "R132") (pin "1") (pinfunction "1_1") (pintype "passive"))
      (node (ref "TP_+5VU") (pin "1") (pinfunction "1_1") (pintype "passive"))
    )
    (net (code "7") (name "/+1V2") (class "Default")
      (node (ref "C145") (pin "1") (pinfunction "1_1") (pintype "passive"))
      (node (ref "IC106") (pin "21") (pinfunction "VREG_1V2_21") (pintype "passive"))
    )
    (net (code "8") (name "/+2V7") (class "Default")
      (node (ref "C144") (pin "1") (pinfunction "1_1") (pintype "passive"))
      (node (ref "IC106") (pin "23") (pinfunction "VREG_2V7_23") (pintype "passive"))
    )
    (net (code "9") (name "/+VCC") (class "Default")
      (node (ref "C137") (pin "1") (pinfunction "1_1") (pintype "passive"))
      (node (ref "IC104") (pin "6") (pinfunction "VCC_6") (pintype "passive"))
      (node (ref "R112") (pin "1") (pinfunction "1_1") (pintype "passive"))
    )
    (net (code "11") (name "/ALERT") (class "Default")
      (node (ref "J103") (pin "4") (pinfunction "4_4") (pintype "passive"))
    )
    (net (code "12") (name "/ALERT_PWR") (class "Default")
      (node (ref "IC106") (pin "19") (pinfunction "ALERT_19") (pintype "passive"))
      (node (ref "J103") (pin "3") (pinfunction "3_3") (pintype "passive"))
    )
    (net (code "13") (name "/CC1") (class "Default")
      (node (ref "CO101") (pin "5") (pinfunction "A5_5") (pintype "passive"))
      (node (ref "D102") (pin "1") (pinfunction "1_1") (pintype "passive"))
      (node (ref "IC106") (pin "1") (pinfunction "CC1DB_1") (pintype "passive"))
      (node (ref "IC106") (pin "2") (pinfunction "CC1_2") (pintype "passive"))
    )
    (net (code "14") (name "/CC2") (class "Default")
      (node (ref "CO101") (pin "25") (pinfunction "B5_25") (pintype "passive"))
      (node (ref "D102") (pin "2") (pinfunction "2_2") (pintype "passive"))
      (node (ref "IC106") (pin "4") (pinfunction "CC2_4") (pintype "passive"))
      (node (ref "IC106") (pin "5") (pinfunction "CC2DB_5") (pintype "passive"))
    )
    (net (code "15") (name "/CPWR_ATTACH") (class "Default")
      (node (ref "R125") (pin "2") (pinfunction "2_2") (pintype "passive"))
    )
    (net (code "16") (name "/CPWR_PWROK2") (class "Default")
      (node (ref "D107") (pin "K") (pinfunction "K_K") (pintype "passive"))
      (node (ref "IC106") (pin "20") (pinfunction "POWER_OK2_20") (pintype "passive"))
    )
    (net (code "17") (name "/CPWR_PWROK3") (class "Default")
      (node (ref "D108") (pin "K") (pinfunction "K_K") (pintype "passive"))
      (node (ref "IC106") (pin "14") (pinfunction "POWER_OK3_14") (pintype "passive"))
    )
    (net (code "18") (name "/I2C0_SCL_Zero") (class "Default")
      (node (ref "IC106") (pin "7") (pinfunction "SCL_7") (pintype "passive"))
      (node (ref "J103") (pin "2") (pinfunction "2_2") (pintype "passive"))
    )
    (net (code "19") (name "/I2C0_SDA_Zero") (class "Default")
      (node (ref "IC106") (pin "8") (pinfunction "SDA_8") (pintype "passive"))
      (node (ref "J103") (pin "1") (pinfunction "1_1") (pintype "passive"))
    )
    (net (code "20") (name "/PGD") (class "Default")
      (node (ref "IC104") (pin "5") (pinfunction "PWRGD_5") (pintype "passive"))
      (node (ref "R112") (pin "2") (pinfunction "2_2") (pintype "passive"))
    )
    (net (code "21") (name "/PHASE") (class "Default")
      (node (ref "C135") (pin "2") (pinfunction "2_2") (pintype "passive"))
      (node (ref "IC104") (pin "9") (pinfunction "PHASE_9") (pintype "passive"))
      (node (ref "L104") (pin "1") (pinfunction "1_1") (pintype "passive"))
      (node (ref "TR102") (pin "1") (pinfunction "S_1") (pintype "passive"))
      (node (ref "TR102") (pin "2") (pinfunction "S_2") (pintype "passive"))
      (node (ref "TR102") (pin "3") (pinfunction "S_3") (pintype "passive"))
      (node (ref "TR103") (pin "5") (pinfunction "D_5") (pintype "passive"))
      (node (ref "TR103") (pin "6") (pinfunction "D_6") (pintype "passive"))
      (node (ref "TR103") (pin "7") (pinfunction "D_7") (pintype "passive"))
      (node (ref "TR103") (pin "8") (pinfunction "D_8") (pintype "passive"))
    )
    (net (code "22") (name "/PWR") (class "Default")
      (node (ref "D101") (pin "K") (pinfunction "K_K") (pintype "passive"))
      (node (ref "F101") (pin "1") (pinfunction "1_1") (pintype "passive"))
      (node (ref "TR101") (pin "3") (pinfunction "S_3") (pintype "passive"))
    )
    (net (code "24") (name "/RESET_PWR") (class "Default")
      (node (ref "IC106") (pin "6") (pinfunction "RESET_6") (pintype "passive"))
      (node (ref "J103") (pin "5") (pinfunction "5_5") (pintype "passive"))
    )
    (net (code "26") (name "/VIN") (class "Default")
      (node (ref "J101") (pin "1") (pinfunction "1_1") (pintype "passive"))
      (node (ref "J102") (pin "1") (pinfunction "1_1") (pintype "passive"))
      (node (ref "TP_VIN") (pin "1") (pinfunction "1_1") (pintype "passive"))
      (node (ref "TR101") (pin "2") (pinfunction "D_2") (pintype "passive"))
    )
    (net (code "28") (name "CPWR") (class "Default")
      (node (ref "CO101") (pin "24") (pinfunction "B4_24") (pintype "passive"))
      (node (ref "CO101") (pin "29") (pinfunction "B9_29") (pintype "passive"))
      (node (ref "CO101") (pin "4") (pinfunction "A4_4") (pintype "passive"))
      (node (ref "CO101") (pin "9") (pinfunction "A9_9") (pintype "passive"))
      (node (ref "IC106") (pin "24") (pinfunction "VDD_24") (pintype "passive"))
      (node (ref "R118") (pin "2") (pinfunction "2_2") (pintype "passive"))
      (node (ref "R122") (pin "1") (pinfunction "1_1") (pintype "passive"))
      (node (ref "TP_CPWR") (pin "1") (pinfunction "1_1") (pintype "passive"))
      (node (ref "TR104") (pin "1") (pinfunction "S_1") (pintype "passive"))
      (node (ref "TR104") (pin "2") (pinfunction "S_2") (pintype "passive"))
      (node (ref "TR104") (pin "3") (pinfunction "S_3") (pintype "passive"))
    )
    (net (code "29") (name "GND") (class "Default")
      (node (ref "C102") (pin "2") (pinfunction "2_2") (pintype "passive"))
      (node (ref "C103") (pin "2") (pinfunction "2_2") (pintype "passive"))
      (node (ref "C104") (pin "2") (pinfunction "2_2") (pintype "passive"))
      (node (ref "C105") (pin "2") (pinfunction "2_2") (pintype "passive"))
      (node (ref "C107") (pin "2") (pinfunction "2_2") (pintype "passive"))
      (node (ref "C108") (pin "2") (pinfunction "2_2") (pintype "passive"))
      (node (ref "C109") (pin "2") (pinfunction "2_2") (pintype "passive"))
      (node (ref "C110") (pin "2") (pinfunction "2_2") (pintype "passive"))
      (node (ref "C111") (pin "2") (pinfunction "2_2") (pintype "passive"))
      (node (ref "C112") (pin "2") (pinfunction "2_2") (pintype "passive"))
      (node (ref "C113") (pin "2") (pinfunction "2_2") (pintype "passive"))
      (node (ref "C114") (pin "2") (pinfunction "2_2") (pintype "passive"))
      (node (ref "C115") (pin "2") (pinfunction "2_2") (pintype "passive"))
      (node (ref "C116") (pin "2") (pinfunction "2_2") (pintype "passive"))
      (node (ref "C118") (pin "2") (pinfunction "2_2") (pintype "passive"))
      (node (ref "C119") (pin "2") (pinfunction "2_2") (pintype "passive"))
      (node (ref "C120") (pin "2") (pinfunction "2_2") (pintype "passive"))
      (node (ref "C121") (pin "2") (pinfunction "2_2") (pintype "passive"))
      (node (ref "C123") (pin "2") (pinfunction "2_2") (pintype "passive"))
      (node (ref "C124") (pin "2") (pinfunction "2_2") (pintype "passive"))
      (node (ref "C125") (pin "2") (pinfunction "2_2") (pintype "passive"))
      (node (ref "C126") (pin "2") (pinfunction "2_2") (pintype "passive"))
      (node (ref "C127") (pin "2") (pinfunction "2_2") (pintype "passive"))
      (node (ref "C128") (pin "2") (pinfunction "2_2") (pintype "passive"))
      (node (ref "C129") (pin "2") (pinfunction "2_2") (pintype "passive"))
      (node (ref "C130") (pin "2") (pinfunction "2_2") (pintype "passive"))
      (node (ref "C131") (pin "2") (pinfunction "2_2") (pintype "passive"))
      (node (ref "C132") (pin "2") (pinfunction "2_2") (pintype "passive"))
      (node (ref "C133") (pin "2") (pinfunction "2_2") (pintype "passive"))
      (node (ref "C134") (pin "2") (pinfunction "2_2") (pintype "passive"))
      (node (ref "C136") (pin "2") (pinfunction "2_2") (pintype "passive"))
      (node (ref "C137") (pin "2") (pinfunction "2_2") (pintype "passive"))
      (node (ref "C139") (pin "2") (pinfunction "2_2") (pintype "passive"))
      (node (ref "C140") (pin "2") (pinfunction "2_2") (pintype "passive"))
      (node (ref "C144") (pin "2") (pinfunction "2_2") (pintype "passive"))
      (node (ref "C145") (pin "2") (pinfunction "2_2") (pintype "passive"))
      (node (ref "C151") (pin "2") (pinfunction "2_2") (pintype "passive"))
      (node (ref "C152") (pin "2") (pinfunction "2_2") (pintype "passive"))
      (node (ref "C153") (pin "2") (pinfunction "2_2") (pintype "passive"))
      (node (ref "C154") (pin "2") (pinfunction "2_2") (pintype "passive"))
      (node (ref "C155") (pin "2") (pinfunction "2_2") (pintype "passive"))
      (node (ref "C156") (pin "2") (pinfunction "2_2") (pintype "passive"))
      (node (ref "C157") (pin "2") (pinfunction "2_2") (pintype "passive"))
      (node (ref "CO101") (pin "1") (pinfunction "A1_1") (pintype "passive"))
      (node (ref "CO101") (pin "12") (pinfunction "A12_12") (pintype "passive"))
      (node (ref "CO101") (pin "21") (pinfunction "B1_21") (pintype "passive"))
      (node (ref "CO101") (pin "32") (pinfunction "B12_32") (pintype "passive"))
      (node (ref "CO101") (pin "SH") (pinfunction "SH_SH") (pintype "power_in"))
      (node (ref "D101") (pin "A") (pinfunction "A_A") (pintype "passive"))
      (node (ref "D102") (pin "3") (pinfunction "GND_3") (pintype "power_in"))
      (node (ref "D103") (pin "K") (pinfunction "K_K") (pintype "passive"))
      (node (ref "D104") (pin "K") (pinfunction "K_K") (pintype "passive"))
      (node (ref "D105") (pin "K") (pinfunction "K_K") (pintype "passive"))
      (node (ref "D106") (pin "K") (pinfunction "K_K") (pintype "passive"))
      (node (ref "IC101") (pin "7") (pinfunction "GND_7") (pintype "passive"))
      (node (ref "IC101") (pin "9") (pinfunction "EP_9") (pintype "passive"))
      (node (ref "IC102") (pin "7") (pinfunction "GND_7") (pintype "passive"))
      (node (ref "IC102") (pin "9") (pinfunction "EP_9") (pintype "passive"))
      (node (ref "IC103") (pin "6") (pinfunction "GND_6") (pintype "passive"))
      (node (ref "IC103") (pin "7") (pinfunction "GND_7") (pintype "passive"))
      (node (ref "IC104") (pin "11") (pinfunction "GND_11") (pintype "passive"))
      (node (ref "IC105") (pin "6") (pinfunction "GND_6") (pintype "passive"))
      (node (ref "IC105") (pin "7") (pinfunction "GND_7") (pintype "passive"))
      (node (ref "IC106") (pin "10") (pinfunction "GND_10") (pintype "passive"))
      (node (ref "IC106") (pin "22") (pinfunction "VSYS_22") (pintype "passive"))
      (node (ref "IC106") (pin "25") (pinfunction "GND_25") (pintype "passive"))
      (node (ref "IC106") (pin "3") (pinfunction "NC_3") (pintype "passive"))
      (node (ref "J101") (pin "2") (pinfunction "2_2") (pintype "passive"))
      (node (ref "J102") (pin "2") (pinfunction "2_2") (pintype "passive"))
      (node (ref "J103") (pin "6") (pinfunction "6_6") (pintype "passive"))
      (node (ref "R104") (pin "1") (pinfunction "1_1") (pintype "passive"))
      (node (ref "R105") (pin "1") (pinfunction "1_1") (pintype "passive"))
      (node (ref "R109") (pin "1") (pinfunction "1_1") (pintype "passive"))
      (node (ref "R117") (pin "1") (pinfunction "1_1") (pintype "passive"))
      (node (ref "R126") (pin "1") (pinfunction "1_1") (pintype "passive"))
      (node (ref "R127") (pin "1") (pinfunction "1_1") (pintype "passive"))
      (node (ref "TP_GND") (pin "1") (pinfunction "1_1") (pintype "passive"))
      (node (ref "TR103") (pin "1") (pinfunction "S_1") (pintype "passive"))
      (node (ref "TR103") (pin "2") (pinfunction "S_2") (pintype "passive"))
      (node (ref "TR103") (pin "3") (pinfunction "S_3") (pintype "passive"))
    )
    (net (code "30") (name "Net-(C101-Pad1)") (class "Default")
      (node (ref "C101") (pin "1") (pinfunction "1_1") (pintype "passive"))
      (node (ref "R101") (pin "1") (pinfunction "1_1") (pintype "passive"))
    )
    (net (code "31") (name "Net-(C116-Pad1)") (class "Default")
      (node (ref "C116") (pin "1") (pinfunction "1_1") (pintype "passive"))
      (node (ref "R103") (pin "1") (pinfunction "1_1") (pintype "passive"))
    )
    (net (code "32") (name "Net-(C117-Pad1)") (class "Default")
      (node (ref "C117") (pin "1") (pinfunction "1_1") (pintype "passive"))
      (node (ref "R106") (pin "1") (pinfunction "1_1") (pintype "passive"))
    )
    (net (code "33") (name "Net-(C131-Pad1)") (class "Default")
      (node (ref "C131") (pin "1") (pinfunction "1_1") (pintype "passive"))
      (node (ref "R108") (pin "1") (pinfunction "1_1") (pintype "passive"))
    )
    (net (code "34") (name "Net-(C138-Pad2)") (class "Default")
      (node (ref "C138") (pin "2") (pinfunction "2_2") (pintype "passive"))
      (node (ref "R114") (pin "2") (pinfunction "2_2") (pintype "passive"))
    )
    (net (code "35") (name "Net-(C142-Pad2)") (class "Default")
      (node (ref "C142") (pin "2") (pinfunction "2_2") (pintype "passive"))
      (node (ref "R116") (pin "1") (pinfunction "1_1") (pintype "passive"))
    )
    (net (code "36") (name "Net-(C143-Pad1)") (class "Default")
      (node (ref "C143") (pin "1") (pinfunction "1_1") (pintype "passive"))
      (node (ref "R119") (pin "2") (pinfunction "2_2") (pintype "passive"))
    )
    (net (code "37") (name "Net-(D103-PadA)") (class "Default")
      (node (ref "D103") (pin "A") (pinfunction "A_A") (pintype "passive"))
      (node (ref "R129") (pin "2") (pinfunction "2_2") (pintype "passive"))
    )
    (net (code "38") (name "Net-(D104-PadA)") (class "Default")
      (node (ref "D104") (pin "A") (pinfunction "A_A") (pintype "passive"))
      (node (ref "R130") (pin "2") (pinfunction "2_2") (pintype "passive"))
    )
    (net (code "39") (name "Net-(D105-PadA)") (class "Default")
      (node (ref "D105") (pin "A") (pinfunction "A_A") (pintype "passive"))
      (node (ref "R131") (pin "2") (pinfunction "2_2") (pintype "passive"))
    )
    (net (code "40") (name "Net-(D106-PadA)") (class "Default")
      (node (ref "D106") (pin "A") (pinfunction "A_A") (pintype "passive"))
      (node (ref "R132") (pin "2") (pinfunction "2_2") (pintype "passive"))
    )
    (net (code "41") (name "Net-(D107-PadA)") (class "Default")
      (node (ref "D107") (pin "A") (pinfunction "A_A") (pintype "passive"))
      (node (ref "R123") (pin "1") (pinfunction "1_1") (pintype "passive"))
    )
    (net (code "42") (name "Net-(D108-PadA)") (class "Default")
      (node (ref "D108") (pin "A") (pinfunction "A_A") (pintype "passive"))
      (node (ref "R124") (pin "1") (pinfunction "1_1") (pintype "passive"))
    )
    (net (code "43") (name "Net-(IC101-BST)") (class "Default")
      (node (ref "C101") (pin "2") (pinfunction "2_2") (pintype "passive"))
      (node (ref "IC101") (pin "1") (pinfunction "BST_1") (pintype "passive"))
    )
    (net (code "44") (name "Net-(IC101-COMP)") (class "Default")
      (node (ref "C115") (pin "1") (pinfunction "1_1") (pintype "passive"))
      (node (ref "IC101") (pin "6") (pinfunction "COMP_6") (pintype "passive"))
      (node (ref "R103") (pin "2") (pinfunction "2_2") (pintype "passive"))
    )
    (net (code "45") (name "Net-(IC101-FB)") (class "Default")
      (node (ref "C106") (pin "2") (pinfunction "2_2") (pintype "passive"))
      (node (ref "IC101") (pin "5") (pinfunction "FB_5") (pintype "passive"))
      (node (ref "R102") (pin "1") (pinfunction "1_1") (pintype "passive"))
      (node (ref "R104") (pin "2") (pinfunction "2_2") (pintype "passive"))
    )
    (net (code "46") (name "Net-(IC101-SS)") (class "Default")
      (node (ref "C114") (pin "1") (pinfunction "1_1") (pintype "passive"))
      (node (ref "IC101") (pin "4") (pinfunction "SS_4") (pintype "passive"))
    )
    (net (code "47") (name "Net-(IC101-SW)") (class "Default")
      (node (ref "IC101") (pin "8") (pinfunction "SW_8") (pintype "passive"))
      (node (ref "L101") (pin "1") (pinfunction "1_1") (pintype "passive"))
      (node (ref "R101") (pin "2") (pinfunction "2_2") (pintype "passive"))
    )
    (net (code "48") (name "Net-(IC102-BST)") (class "Default")
      (node (ref "C117") (pin "2") (pinfunction "2_2") (pintype "passive"))
      (node (ref "IC102") (pin "1") (pinfunction "BST_1") (pintype "passive"))
    )
    (net (code "49") (name "Net-(IC102-COMP)") (class "Default")
      (node (ref "C130") (pin "1") (pinfunction "1_1") (pintype "passive"))
      (node (ref "IC102") (pin "6") (pinfunction "COMP_6") (pintype "passive"))
      (node (ref "R108") (pin "2") (pinfunction "2_2") (pintype "passive"))
    )
    (net (code "50") (name "Net-(IC102-FB)") (class "Default")
      (node (ref "C122") (pin "2") (pinfunction "2_2") (pintype "passive"))
      (node (ref "IC102") (pin "5") (pinfunction "FB_5") (pintype "passive"))
      (node (ref "R107") (pin "1") (pinfunction "1_1") (pintype "passive"))
      (node (ref "R109") (pin "2") (pinfunction "2_2") (pintype "passive"))
    )
    (net (code "51") (name "Net-(IC102-SS)") (class "Default")
      (node (ref "C129") (pin "1") (pinfunction "1_1") (pintype "passive"))
      (node (ref "IC102") (pin "4") (pinfunction "SS_4") (pintype "passive"))
    )
    (net (code "52") (name "Net-(IC102-SW)") (class "Default")
      (node (ref "IC102") (pin "8") (pinfunction "SW_8") (pintype "passive"))
      (node (ref "L102") (pin "1") (pinfunction "1_1") (pintype "passive"))
      (node (ref "R106") (pin "2") (pinfunction "2_2") (pintype "passive"))
    )
    (net (code "53") (name "Net-(IC103-PG)") (class "Default")
      (node (ref "IC103") (pin "2") (pinfunction "PG_2") (pintype "passive"))
      (node (ref "R110") (pin "2") (pinfunction "2_2") (pintype "passive"))
    )
    (net (code "54") (name "Net-(IC103-SW)") (class "Default")
      (node (ref "IC103") (pin "1") (pinfunction "SW_1") (pintype "passive"))
      (node (ref "L103") (pin "1") (pinfunction "1_1") (pintype "passive"))
    )
    (net (code "55") (name "Net-(IC104-BOOT)") (class "Default")
      (node (ref "C135") (pin "1") (pinfunction "1_1") (pintype "passive"))
      (node (ref "IC104") (pin "8") (pinfunction "BOOT_8") (pintype "passive"))
    )
    (net (code "56") (name "Net-(IC104-COMP)") (class "Default")
      (node (ref "C138") (pin "1") (pinfunction "1_1") (pintype "passive"))
      (node (ref "C141") (pin "1") (pinfunction "1_1") (pintype "passive"))
      (node (ref "IC104") (pin "3") (pinfunction "COMP_3") (pintype "passive"))
    )
    (net (code "57") (name "Net-(IC104-FB)") (class "Default")
      (node (ref "C141") (pin "2") (pinfunction "2_2") (pintype "passive"))
      (node (ref "C142") (pin "1") (pinfunction "1_1") (pintype "passive"))
      (node (ref "IC104") (pin "2") (pinfunction "FB_2") (pintype "passive"))
      (node (ref "R114") (pin "1") (pinfunction "1_1") (pintype "passive"))
      (node (ref "R115") (pin "1") (pinfunction "1_1") (pintype "passive"))
      (node (ref "R117") (pin "2") (pinfunction "2_2") (pintype "passive"))
    )
    (net (code "58") (name "Net-(IC104-HDRV)") (class "Default")
      (node (ref "IC104") (pin "10") (pinfunction "HDRV_10") (pintype "passive"))
      (node (ref "TR102") (pin "4") (pinfunction "G_4") (pintype "passive"))
    )
    (net (code "59") (name "Net-(IC104-LDRV)") (class "Default")
      (node (ref "IC104") (pin "7") (pinfunction "LDRV_7") (pintype "passive"))
      (node (ref "TR103") (pin "4") (pinfunction "G_4") (pintype "passive"))
    )
    (net (code "60") (name "Net-(IC104-SHDN)") (class "Default")
      (node (ref "IC104") (pin "1") (pinfunction "SHDN_1") (pintype "passive"))
      (node (ref "R111") (pin "2") (pinfunction "2_2") (pintype "passive"))
    )
    (net (code "61") (name "Net-(IC105-PG)") (class "Default")
      (node (ref "IC105") (pin "2") (pinfunction "PG_2") (pintype "passive"))
      (node (ref "R113") (pin "2") (pinfunction "2_2") (pintype "passive"))
    )
    (net (code "62") (name "Net-(IC105-SW)") (class "Default")
      (node (ref "IC105") (pin "1") (pinfunction "SW_1") (pintype "passive"))
      (node (ref "L105") (pin "1") (pinfunction "1_1") (pintype "passive"))
    )
    (net (code "63") (name "Net-(IC106-ADDR0)") (class "Default")
      (node (ref "IC106") (pin "12") (pinfunction "ADDR0_12") (pintype "passive"))
      (node (ref "R126") (pin "2") (pinfunction "2_2") (pintype "passive"))
    )
    (net (code "64") (name "Net-(IC106-ADDR1)") (class "Default")
      (node (ref "IC106") (pin "13") (pinfunction "ADDR1_13") (pintype "passive"))
      (node (ref "R127") (pin "2") (pinfunction "2_2") (pintype "passive"))
    )
    (net (code "65") (name "Net-(IC106-ATTACH)") (class "Default")
      (node (ref "IC106") (pin "11") (pinfunction "ATTACH_11") (pintype "passive"))
      (node (ref "R125") (pin "1") (pinfunction "1_1") (pintype "passive"))
    )
    (net (code "66") (name "Net-(IC106-DISCH)") (class "Default")
      (node (ref "IC106") (pin "9") (pinfunction "DISCH_9") (pintype "passive"))
      (node (ref "R121") (pin "1") (pinfunction "1_1") (pintype "passive"))
    )
    (net (code "67") (name "Net-(IC106-VBUS_EN_SNK)") (class "Default")
      (node (ref "IC106") (pin "16") (pinfunction "VBUS_EN_SNK_16") (pintype "passive"))
      (node (ref "R120") (pin "1") (pinfunction "1_1") (pintype "passive"))
    )
    (net (code "68") (name "Net-(IC106-VBUS_VS_DISCH)") (class "Default")
      (node (ref "IC106") (pin "18") (pinfunction "VBUS_VS_DISCH_18") (pintype "passive"))
      (node (ref "R122") (pin "2") (pinfunction "2_2") (pintype "passive"))
    )
    (net (code "69") (name "Net-(TR101-G)") (class "Default")
      (node (ref "R105") (pin "2") (pinfunction "2_2") (pintype "passive"))
      (node (ref "TR101") (pin "1") (pinfunction "G_1") (pintype "passive"))
    )
    (net (code "70") (name "Net-(TR104-G)") (class "Default")
      (node (ref "R118") (pin "1") (pinfunction "1_1") (pintype "passive"))
      (node (ref "R119") (pin "1") (pinfunction "1_1") (pintype "passive"))
      (node (ref "R120") (pin "2") (pinfunction "2_2") (pintype "passive"))
      (node (ref "TR104") (pin "4") (pinfunction "G_4") (pintype "passive"))
    )
    (net (code "71") (name "VPWR") (class "Default")
      (node (ref "C107") (pin "1") (pinfunction "1_1") (pintype "passive"))
      (node (ref "C108") (pin "1") (pinfunction "1_1") (pintype "passive"))
      (node (ref "C109") (pin "1") (pinfunction "1_1") (pintype "passive"))
      (node (ref "C110") (pin "1") (pinfunction "1_1") (pintype "passive"))
      (node (ref "C111") (pin "1") (pinfunction "1_1") (pintype "passive"))
      (node (ref "C112") (pin "1") (pinfunction "1_1") (pintype "passive"))
      (node (ref "C113") (pin "1") (pinfunction "1_1") (pintype "passive"))
      (node (ref "C123") (pin "1") (pinfunction "1_1") (pintype "passive"))
      (node (ref "C124") (pin "1") (pinfunction "1_1") (pintype "passive"))
      (node (ref "C125") (pin "1") (pinfunction "1_1") (pintype "passive"))
      (node (ref "C126") (pin "1") (pinfunction "1_1") (pintype "passive"))
      (node (ref "C127") (pin "1") (pinfunction "1_1") (pintype "passive"))
      (node (ref "C128") (pin "1") (pinfunction "1_1") (pintype "passive"))
      (node (ref "C132") (pin "1") (pinfunction "1_1") (pintype "passive"))
      (node (ref "C143") (pin "2") (pinfunction "2_2") (pintype "passive"))
      (node (ref "C151") (pin "1") (pinfunction "1_1") (pintype "passive"))
      (node (ref "C152") (pin "1") (pinfunction "1_1") (pintype "passive"))
      (node (ref "C153") (pin "1") (pinfunction "1_1") (pintype "passive"))
      (node (ref "C154") (pin "1") (pinfunction "1_1") (pintype "passive"))
      (node (ref "F101") (pin "2") (pinfunction "2_2") (pintype "passive"))
      (node (ref "IC101") (pin "2") (pinfunction "Vin_2") (pintype "passive"))
      (node (ref "IC101") (pin "3") (pinfunction "EN_3") (pintype "passive"))
      (node (ref "IC102") (pin "2") (pinfunction "Vin_2") (pintype "passive"))
      (node (ref "IC102") (pin "3") (pinfunction "EN_3") (pintype "passive"))
      (node (ref "IC104") (pin "4") (pinfunction "Vin_4") (pintype "passive"))
      (node (ref "R111") (pin "1") (pinfunction "1_1") (pintype "passive"))
      (node (ref "R121") (pin "2") (pinfunction "2_2") (pintype "passive"))
      (node (ref "R123") (pin "2") (pinfunction "2_2") (pintype "passive"))
      (node (ref "R124") (pin "2") (pinfunction "2_2") (pintype "passive"))
      (node (ref "R130") (pin "1") (pinfunction "1_1") (pintype "passive"))
      (node (ref "TP_VPWR") (pin "1") (pinfunction "1_1") (pintype "passive"))
      (node (ref "TR102") (pin "5") (pinfunction "D_5") (pintype "passive"))
      (node (ref "TR102") (pin "6") (pinfunction "D_6") (pintype "passive"))
      (node (ref "TR102") (pin "7") (pinfunction "D_7") (pintype "passive"))
      (node (ref "TR102") (pin "8") (pinfunction "D_8") (pintype "passive"))
      (node (ref "TR104") (pin "5") (pinfunction "D_5") (pintype "passive"))
      (node (ref "TR104") (pin "6") (pinfunction "D_6") (pintype "passive"))
      (node (ref "TR104") (pin "7") (pinfunction "D_7") (pintype "passive"))
      (node (ref "TR104") (pin "8") (pinfunction "D_8") (pintype "passive"))
    )
    (net (code "72") (name "unconnected-(CO101-A2-Pad2)") (class "Default")
      (node (ref "CO101") (pin "2") (pinfunction "A2_2") (pintype "passive"))
    )
    (net (code "73") (name "unconnected-(CO101-A3-Pad3)") (class "Default")
      (node (ref "CO101") (pin "3") (pinfunction "A3_3") (pintype "passive"))
    )
    (net (code "74") (name "unconnected-(CO101-A6-Pad6)") (class "Default")
      (node (ref "CO101") (pin "6") (pinfunction "A6_6") (pintype "passive"))
    )
    (net (code "75") (name "unconnected-(CO101-A7-Pad7)") (class "Default")
      (node (ref "CO101") (pin "7") (pinfunction "A7_7") (pintype "passive"))
    )
    (net (code "76") (name "unconnected-(CO101-A8-Pad8)") (class "Default")
      (node (ref "CO101") (pin "8") (pinfunction "A8_8") (pintype "passive"))
    )
    (net (code "77") (name "unconnected-(CO101-A10-Pad10)") (class "Default")
      (node (ref "CO101") (pin "10") (pinfunction "A10_10") (pintype "passive"))
    )
    (net (code "78") (name "unconnected-(CO101-A11-Pad11)") (class "Default")
      (node (ref "CO101") (pin "11") (pinfunction "A11_11") (pintype "passive"))
    )
    (net (code "79") (name "unconnected-(CO101-B2-Pad22)") (class "Default")
      (node (ref "CO101") (pin "22") (pinfunction "B2_22") (pintype "passive"))
    )
    (net (code "80") (name "unconnected-(CO101-B3-Pad23)") (class "Default")
      (node (ref "CO101") (pin "23") (pinfunction "B3_23") (pintype "passive"))
    )
    (net (code "81") (name "unconnected-(CO101-B6-Pad26)") (class "Default")
      (node (ref "CO101") (pin "26") (pinfunction "B6_26") (pintype "passive"))
    )
    (net (code "82") (name "unconnected-(CO101-B7-Pad27)") (class "Default")
      (node (ref "CO101") (pin "27") (pinfunction "B7_27") (pintype "passive"))
    )
    (net (code "83") (name "unconnected-(CO101-B8-Pad28)") (class "Default")
      (node (ref "CO101") (pin "28") (pinfunction "B8_28") (pintype "passive"))
    )
    (net (code "84") (name "unconnected-(CO101-B10-Pad30)") (class "Default")
      (node (ref "CO101") (pin "30") (pinfunction "B10_30") (pintype "passive"))
    )
    (net (code "85") (name "unconnected-(CO101-B11-Pad31)") (class "Default")
      (node (ref "CO101") (pin "31") (pinfunction "B11_31") (pintype "passive"))
    )
    (net (code "86") (name "unconnected-(IC106-A_B_SIDE-Pad17)") (class "Default")
      (node (ref "IC106") (pin "17") (pinfunction "A_B_SIDE_17") (pintype "passive+no_connect"))
    )
    (net (code "87") (name "unconnected-(IC106-GPIO-Pad15)") (class "Default")
      (node (ref "IC106") (pin "15") (pinfunction "GPIO_15") (pintype "passive"))
    )
  )
)
